# Board2_1.net
KiCad netlist of a schematic drawn in EAGLE
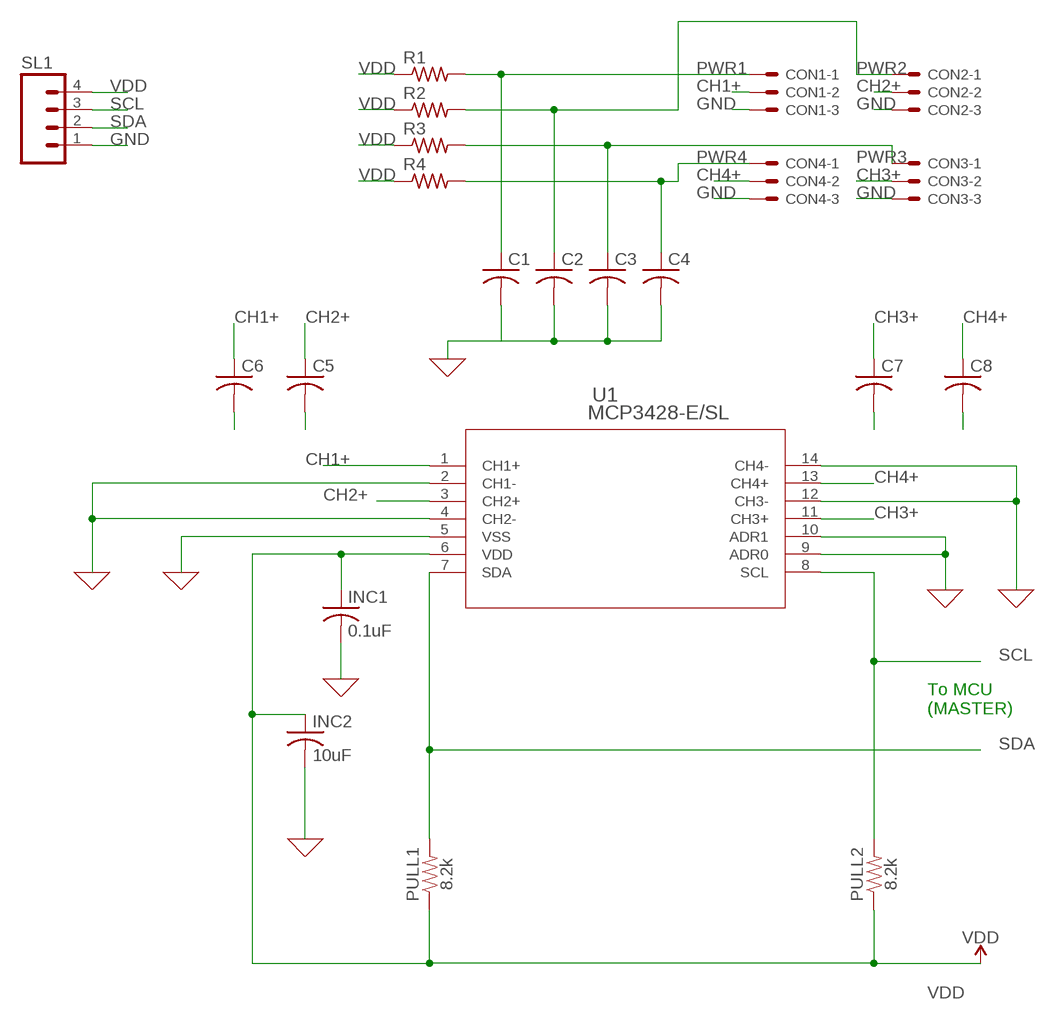
[diagram p0: schematic, sheet 1]

(export (version "E")
  (design (tool "Eeschema 10.0.6"))
  (components
    (comp (ref "C1")
      (value "C-USC0805")
      (footprint "eagle-import:C0805")
      (libsource (lib "eagle-import") (part "C-USC0805"))
    )
    (comp (ref "C2")
      (value "C-USC0805")
      (footprint "eagle-import:C0805")
      (libsource (lib "eagle-import") (part "C-USC0805"))
    )
    (comp (ref "C3")
      (value "C-USC0805")
      (footprint "eagle-import:C0805")
      (libsource (lib "eagle-import") (part "C-USC0805"))
    )
    (comp (ref "C4")
      (value "C-USC0805")
      (footprint "eagle-import:C0805")
      (libsource (lib "eagle-import") (part "C-USC0805"))
    )
    (comp (ref "C5")
      (value "C-USC0805")
      (footprint "eagle-import:C0805")
      (libsource (lib "eagle-import") (part "C-USC0805"))
    )
    (comp (ref "C6")
      (value "C-USC0805")
      (footprint "eagle-import:C0805")
      (libsource (lib "eagle-import") (part "C-USC0805"))
    )
    (comp (ref "C7")
      (value "C-USC0805")
      (footprint "eagle-import:C0805")
      (libsource (lib "eagle-import") (part "C-USC0805"))
    )
    (comp (ref "C8")
      (value "C-USC0805")
      (footprint "eagle-import:C0805")
      (libsource (lib "eagle-import") (part "C-USC0805"))
    )
    (comp (ref "CON1")
      (value "KK-156-3")
      (footprint "eagle-import:KK-156-3")
      (libsource (lib "eagle-import") (part "KK-156-3"))
    )
    (comp (ref "CON2")
      (value "KK-156-3")
      (footprint "eagle-import:KK-156-3")
      (libsource (lib "eagle-import") (part "KK-156-3"))
    )
    (comp (ref "CON3")
      (value "KK-156-3")
      (footprint "eagle-import:KK-156-3")
      (libsource (lib "eagle-import") (part "KK-156-3"))
    )
    (comp (ref "CON4")
      (value "KK-156-3")
      (footprint "eagle-import:KK-156-3")
      (libsource (lib "eagle-import") (part "KK-156-3"))
    )
    (comp (ref "INC1")
      (value "0.1uF")
      (footprint "eagle-import:C0805K")
      (libsource (lib "eagle-import") (part "C-USC0805K"))
    )
    (comp (ref "INC2")
      (value "10uF")
      (footprint "eagle-import:C0805K")
      (libsource (lib "eagle-import") (part "C-USC0805K"))
    )
    (comp (ref "PULL1")
      (value "8.2k")
      (footprint "eagle-import:0603")
      (libsource (lib "eagle-import") (part "8.2KOHM-0603-1/10W-5%"))
    )
    (comp (ref "PULL2")
      (value "8.2k")
      (footprint "eagle-import:0603")
      (libsource (lib "eagle-import") (part "8.2KOHM-0603-1/10W-5%"))
    )
    (comp (ref "R1")
      (value "R-US_R0805")
      (footprint "eagle-import:R0805")
      (libsource (lib "eagle-import") (part "R-US_R0805"))
    )
    (comp (ref "R2")
      (value "R-US_R0805")
      (footprint "eagle-import:R0805")
      (libsource (lib "eagle-import") (part "R-US_R0805"))
    )
    (comp (ref "R3")
      (value "R-US_R0805")
      (footprint "eagle-import:R0805")
      (libsource (lib "eagle-import") (part "R-US_R0805"))
    )
    (comp (ref "R4")
      (value "R-US_R0805")
      (footprint "eagle-import:R0805")
      (libsource (lib "eagle-import") (part "R-US_R0805"))
    )
    (comp (ref "SL1")
      (value "MA04")
      (footprint "eagle-import:04PA")
      (libsource (lib "eagle-import") (part "MA04"))
    )
    (comp (ref "U1")
      (value "MCP3428-E/SL")
      (footprint "eagle-import:SOIC14-N_MC")
      (fields (field (name "MANUFACTURER_PART_NUMBER") "MCP3428ESL"))
      (libsource (lib "eagle-import") (part "MCP3428-E/SL"))
    )
  )
  (nets
    (net (code "1") (name "/CH1+") (class "Default")
      (node (ref "C6") (pin "1") (pinfunction "1_1") (pintype "passive"))
      (node (ref "CON1") (pin "2") (pinfunction "S_2") (pintype "passive"))
      (node (ref "U1") (pin "1") (pinfunction "CH1+_1") (pintype "input"))
    )
    (net (code "2") (name "/CH2+") (class "Default")
      (node (ref "C5") (pin "1") (pinfunction "1_1") (pintype "passive"))
      (node (ref "CON2") (pin "2") (pinfunction "S_2") (pintype "passive"))
      (node (ref "U1") (pin "3") (pinfunction "CH2+_3") (pintype "input"))
    )
    (net (code "3") (name "/CH3+") (class "Default")
      (node (ref "C7") (pin "1") (pinfunction "1_1") (pintype "passive"))
      (node (ref "CON3") (pin "2") (pinfunction "S_2") (pintype "passive"))
      (node (ref "U1") (pin "11") (pinfunction "CH3+_11") (pintype "input"))
    )
    (net (code "4") (name "/CH4+") (class "Default")
      (node (ref "C8") (pin "1") (pinfunction "1_1") (pintype "passive"))
      (node (ref "CON4") (pin "2") (pinfunction "S_2") (pintype "passive"))
      (node (ref "U1") (pin "13") (pinfunction "CH4+_13") (pintype "input"))
    )
    (net (code "5") (name "/PWR1") (class "Default")
      (node (ref "C1") (pin "1") (pinfunction "1_1") (pintype "passive"))
      (node (ref "CON1") (pin "1") (pinfunction "S_1") (pintype "passive"))
      (node (ref "R1") (pin "2") (pinfunction "2_2") (pintype "passive"))
    )
    (net (code "6") (name "/PWR2") (class "Default")
      (node (ref "C2") (pin "1") (pinfunction "1_1") (pintype "passive"))
      (node (ref "CON2") (pin "1") (pinfunction "S_1") (pintype "passive"))
      (node (ref "R2") (pin "2") (pinfunction "2_2") (pintype "passive"))
    )
    (net (code "7") (name "/PWR3") (class "Default")
      (node (ref "C3") (pin "1") (pinfunction "1_1") (pintype "passive"))
      (node (ref "CON3") (pin "1") (pinfunction "S_1") (pintype "passive"))
      (node (ref "R3") (pin "2") (pinfunction "2_2") (pintype "passive"))
    )
    (net (code "8") (name "/PWR4") (class "Default")
      (node (ref "C4") (pin "1") (pinfunction "1_1") (pintype "passive"))
      (node (ref "CON4") (pin "1") (pinfunction "S_1") (pintype "passive"))
      (node (ref "R4") (pin "2") (pinfunction "2_2") (pintype "passive"))
    )
    (net (code "9") (name "/SCL") (class "Default")
      (node (ref "PULL2") (pin "2") (pinfunction "2_2") (pintype "passive"))
      (node (ref "SL1") (pin "3") (pinfunction "3_3") (pintype "passive"))
      (node (ref "U1") (pin "8") (pinfunction "SCL_8") (pintype "input"))
    )
    (net (code "10") (name "/SDA") (class "Default")
      (node (ref "PULL1") (pin "2") (pinfunction "2_2") (pintype "passive"))
      (node (ref "SL1") (pin "2") (pinfunction "2_2") (pintype "passive"))
      (node (ref "U1") (pin "7") (pinfunction "SDA_7") (pintype "bidirectional"))
    )
    (net (code "11") (name "GND") (class "Default")
      (node (ref "C1") (pin "2") (pinfunction "2_2") (pintype "passive"))
      (node (ref "C2") (pin "2") (pinfunction "2_2") (pintype "passive"))
      (node (ref "C3") (pin "2") (pinfunction "2_2") (pintype "passive"))
      (node (ref "C4") (pin "2") (pinfunction "2_2") (pintype "passive"))
      (node (ref "C5") (pin "2") (pinfunction "2_2") (pintype "passive"))
      (node (ref "C6") (pin "2") (pinfunction "2_2") (pintype "passive"))
      (node (ref "C7") (pin "2") (pinfunction "2_2") (pintype "passive"))
      (node (ref "C8") (pin "2") (pinfunction "2_2") (pintype "passive"))
      (node (ref "CON1") (pin "3") (pinfunction "S_3") (pintype "passive"))
      (node (ref "CON2") (pin "3") (pinfunction "S_3") (pintype "passive"))
      (node (ref "CON3") (pin "3") (pinfunction "S_3") (pintype "passive"))
      (node (ref "CON4") (pin "3") (pinfunction "S_3") (pintype "passive"))
      (node (ref "INC1") (pin "2") (pinfunction "2_2") (pintype "passive"))
      (node (ref "INC2") (pin "2") (pinfunction "2_2") (pintype "passive"))
      (node (ref "SL1") (pin "1") (pinfunction "1_1") (pintype "passive"))
      (node (ref "U1") (pin "10") (pinfunction "ADR1_10") (pintype "passive"))
      (node (ref "U1") (pin "12") (pinfunction "CH3-_12") (pintype "input"))
      (node (ref "U1") (pin "14") (pinfunction "CH4-_14") (pintype "input"))
      (node (ref "U1") (pin "2") (pinfunction "CH1-_2") (pintype "input"))
      (node (ref "U1") (pin "4") (pinfunction "CH2-_4") (pintype "input"))
      (node (ref "U1") (pin "5") (pinfunction "VSS_5") (pintype "power_in"))
      (node (ref "U1") (pin "9") (pinfunction "ADR0_9") (pintype "passive"))
    )
    (net (code "12") (name "VDD") (class "Default")
      (node (ref "INC1") (pin "1") (pinfunction "1_1") (pintype "passive"))
      (node (ref "INC2") (pin "1") (pinfunction "1_1") (pintype "passive"))
      (node (ref "PULL1") (pin "1") (pinfunction "1_1") (pintype "passive"))
      (node (ref "PULL2") (pin "1") (pinfunction "1_1") (pintype "passive"))
      (node (ref "R1") (pin "1") (pinfunction "1_1") (pintype "passive"))
      (node (ref "R2") (pin "1") (pinfunction "1_1") (pintype "passive"))
      (node (ref "R3") (pin "1") (pinfunction "1_1") (pintype "passive"))
      (node (ref "R4") (pin "1") (pinfunction "1_1") (pintype "passive"))
      (node (ref "SL1") (pin "4") (pinfunction "4_4") (pintype "passive"))
      (node (ref "U1") (pin "6") (pinfunction "VDD_6") (pintype "power_in"))
    )
  )
)
